# ATRACK_KEY_V2.net
KiCad netlist of a schematic drawn in Altium Designer
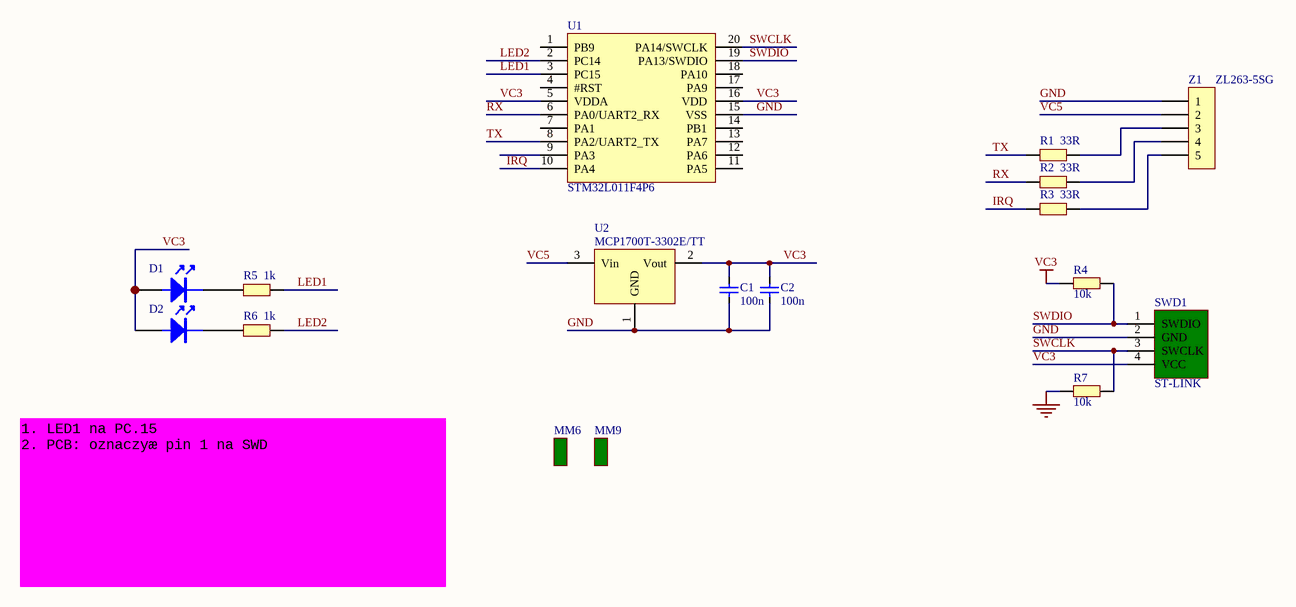
[diagram p0: ATRACK_KEY_V2.SchDoc]

(export (version "E")
  (design (tool "Eeschema 10.0.6"))
  (components
    (comp (ref "C1") (value "100n") (footprint "0603C") (libsource (lib "*") (part "CAP")))
    (comp (ref "C2") (value "100n") (footprint "0603C") (libsource (lib "*") (part "CAP")))
    (comp (ref "D1") (value "~") (footprint "0603LG") (libsource (lib "*") (part "LED")))
    (comp (ref "D2") (value "~") (footprint "0603LR") (libsource (lib "*") (part "LED")))
    (comp (ref "MM6") (value "~") (footprint "REF_CIR") (libsource (lib "*") (part "MECH")))
    (comp (ref "MM9") (value "~") (footprint "REF_SQR") (libsource (lib "*") (part "MECH")))
    (comp (ref "R1") (value "33R") (footprint "0603R") (libsource (lib "*") (part "RES3")))
    (comp (ref "R2") (value "33R") (footprint "0603R") (libsource (lib "*") (part "RES3")))
    (comp (ref "R3") (value "33R") (footprint "0603R") (libsource (lib "*") (part "RES3")))
    (comp (ref "R4") (value "10k") (footprint "0603R") (libsource (lib "*") (part "RES3")))
    (comp (ref "R5") (value "1k") (footprint "0603R") (libsource (lib "*") (part "RES3")))
    (comp (ref "R6") (value "1k") (footprint "0603R") (libsource (lib "*") (part "RES3")))
    (comp (ref "R7") (value "10k") (footprint "0603R") (libsource (lib "*") (part "RES3")))
    (comp (ref "SWD1")
      (value "ST-LINK")
      (footprint "PIN4")
      (description "Header, 4-Pin")
      (fields (field (name "PUBLISHER") "Altium Limited"))
      (libsource (lib "GkSchlib") (part "SW_CON"))
    )
    (comp (ref "U1")
      (value "STM32L011F4P6")
      (footprint "TSSOP20")
      (libsource (lib "GkSchlib") (part "STM32L011F4P6"))
    )
    (comp (ref "U2")
      (value "MCP1700T-3302E/TT")
      (footprint "SOT-23")
      (libsource (lib "*") (part "MCP1700T-3302E/TT"))
    )
    (comp (ref "Z1")
      (value "ZL263-5SG")
      (footprint "PIN5_ZL")
      (description "Connector")
      (libsource (lib "*") (part "CON5"))
    )
  )
  (nets
    (net (code "1") (name "/IRQ") (class "Default")
      (node (ref "R3") (pin "1") (pintype "passive"))
      (node (ref "U1") (pin "10") (pinfunction "PA4_10") (pintype "passive"))
    )
    (net (code "2") (name "/LED1") (class "Default")
      (node (ref "R5") (pin "2") (pintype "passive"))
      (node (ref "U1") (pin "3") (pinfunction "PC15_3") (pintype "passive"))
    )
    (net (code "3") (name "/LED2") (class "Default")
      (node (ref "R6") (pin "2") (pintype "passive"))
      (node (ref "U1") (pin "2") (pinfunction "PC14_2") (pintype "passive"))
    )
    (net (code "4") (name "/RX") (class "Default")
      (node (ref "R2") (pin "1") (pintype "passive"))
      (node (ref "U1") (pin "6") (pinfunction "PA0/UART2_RX_6") (pintype "passive"))
    )
    (net (code "5") (name "/SWCLK") (class "Default")
      (node (ref "R7") (pin "2") (pintype "passive"))
      (node (ref "SWD1") (pin "3") (pinfunction "SWCLK_3") (pintype "passive"))
      (node (ref "U1") (pin "20") (pinfunction "PA14/SWCLK_20") (pintype "passive"))
    )
    (net (code "6") (name "/SWDIO") (class "Default")
      (node (ref "R4") (pin "2") (pintype "passive"))
      (node (ref "SWD1") (pin "1") (pinfunction "SWDIO_1") (pintype "passive"))
      (node (ref "U1") (pin "19") (pinfunction "PA13/SWDIO_19") (pintype "passive"))
    )
    (net (code "7") (name "/TX") (class "Default")
      (node (ref "R1") (pin "1") (pintype "passive"))
      (node (ref "U1") (pin "8") (pinfunction "PA2/UART2_TX_8") (pintype "passive"))
    )
    (net (code "8") (name "/VC5") (class "Default")
      (node (ref "U2") (pin "3") (pinfunction "Vin_3") (pintype "passive"))
      (node (ref "Z1") (pin "2") (pinfunction "2_2") (pintype "passive"))
    )
    (net (code "9") (name "GND") (class "Default")
      (node (ref "C1") (pin "2") (pintype "passive"))
      (node (ref "C2") (pin "2") (pintype "passive"))
      (node (ref "R7") (pin "1") (pintype "passive"))
      (node (ref "SWD1") (pin "2") (pinfunction "GND_2") (pintype "passive"))
      (node (ref "U1") (pin "15") (pinfunction "VSS_15") (pintype "passive"))
      (node (ref "U2") (pin "1") (pinfunction "GND_1") (pintype "passive"))
      (node (ref "Z1") (pin "1") (pinfunction "1_1") (pintype "passive"))
    )
    (net (code "10") (name "Net-(D1-2)") (class "Default")
      (node (ref "D1") (pin "K") (pinfunction "2_K") (pintype "passive"))
      (node (ref "R5") (pin "1") (pintype "passive"))
    )
    (net (code "11") (name "Net-(D2-2)") (class "Default")
      (node (ref "D2") (pin "K") (pinfunction "2_K") (pintype "passive"))
      (node (ref "R6") (pin "1") (pintype "passive"))
    )
    (net (code "12") (name "Net-(R1-Pad2)") (class "Default")
      (node (ref "R1") (pin "2") (pintype "passive"))
      (node (ref "Z1") (pin "3") (pinfunction "3_3") (pintype "passive"))
    )
    (net (code "13") (name "Net-(R2-Pad2)") (class "Default")
      (node (ref "R2") (pin "2") (pintype "passive"))
      (node (ref "Z1") (pin "4") (pinfunction "4_4") (pintype "passive"))
    )
    (net (code "14") (name "Net-(R3-Pad2)") (class "Default")
      (node (ref "R3") (pin "2") (pintype "passive"))
      (node (ref "Z1") (pin "5") (pinfunction "5_5") (pintype "passive"))
    )
    (net (code "15") (name "VC3") (class "Default")
      (node (ref "C1") (pin "1") (pintype "passive"))
      (node (ref "C2") (pin "1") (pintype "passive"))
      (node (ref "D1") (pin "A") (pinfunction "1_A") (pintype "passive"))
      (node (ref "D2") (pin "A") (pinfunction "1_A") (pintype "passive"))
      (node (ref "R4") (pin "1") (pintype "passive"))
      (node (ref "SWD1") (pin "4") (pinfunction "VCC_4") (pintype "passive"))
      (node (ref "U1") (pin "16") (pinfunction "VDD_16") (pintype "passive"))
      (node (ref "U1") (pin "5") (pinfunction "VDDA_5") (pintype "passive"))
      (node (ref "U2") (pin "2") (pinfunction "Vout_2") (pintype "passive"))
    )
    (net (code "16") (name "unconnected-(U1-#RST-Pad4)") (class "Default")
      (node (ref "U1") (pin "4") (pinfunction "#RST_4") (pintype "passive"))
    )
    (net (code "17") (name "unconnected-(U1-PA1-Pad7)") (class "Default")
      (node (ref "U1") (pin "7") (pinfunction "PA1_7") (pintype "passive"))
    )
    (net (code "18") (name "unconnected-(U1-PA3-Pad9)") (class "Default")
      (node (ref "U1") (pin "9") (pinfunction "PA3_9") (pintype "passive"))
    )
    (net (code "19") (name "unconnected-(U1-PA5-Pad11)") (class "Default")
      (node (ref "U1") (pin "11") (pinfunction "PA5_11") (pintype "passive"))
    )
    (net (code "20") (name "unconnected-(U1-PA6-Pad12)") (class "Default")
      (node (ref "U1") (pin "12") (pinfunction "PA6_12") (pintype "passive"))
    )
    (net (code "21") (name "unconnected-(U1-PA7-Pad13)") (class "Default")
      (node (ref "U1") (pin "13") (pinfunction "PA7_13") (pintype "passive"))
    )
    (net (code "22") (name "unconnected-(U1-PA9-Pad17)") (class "Default")
      (node (ref "U1") (pin "17") (pinfunction "PA9_17") (pintype "passive"))
    )
    (net (code "23") (name "unconnected-(U1-PA10-Pad18)") (class "Default")
      (node (ref "U1") (pin "18") (pinfunction "PA10_18") (pintype "passive"))
    )
    (net (code "24") (name "unconnected-(U1-PB1-Pad14)") (class "Default")
      (node (ref "U1") (pin "14") (pinfunction "PB1_14") (pintype "passive"))
    )
    (net (code "25") (name "unconnected-(U1-PB9-Pad1)") (class "Default")
      (node (ref "U1") (pin "1") (pinfunction "PB9_1") (pintype "passive"))
    )
  )
)
